# MotorController.net
KiCad netlist of a schematic drawn in EAGLE
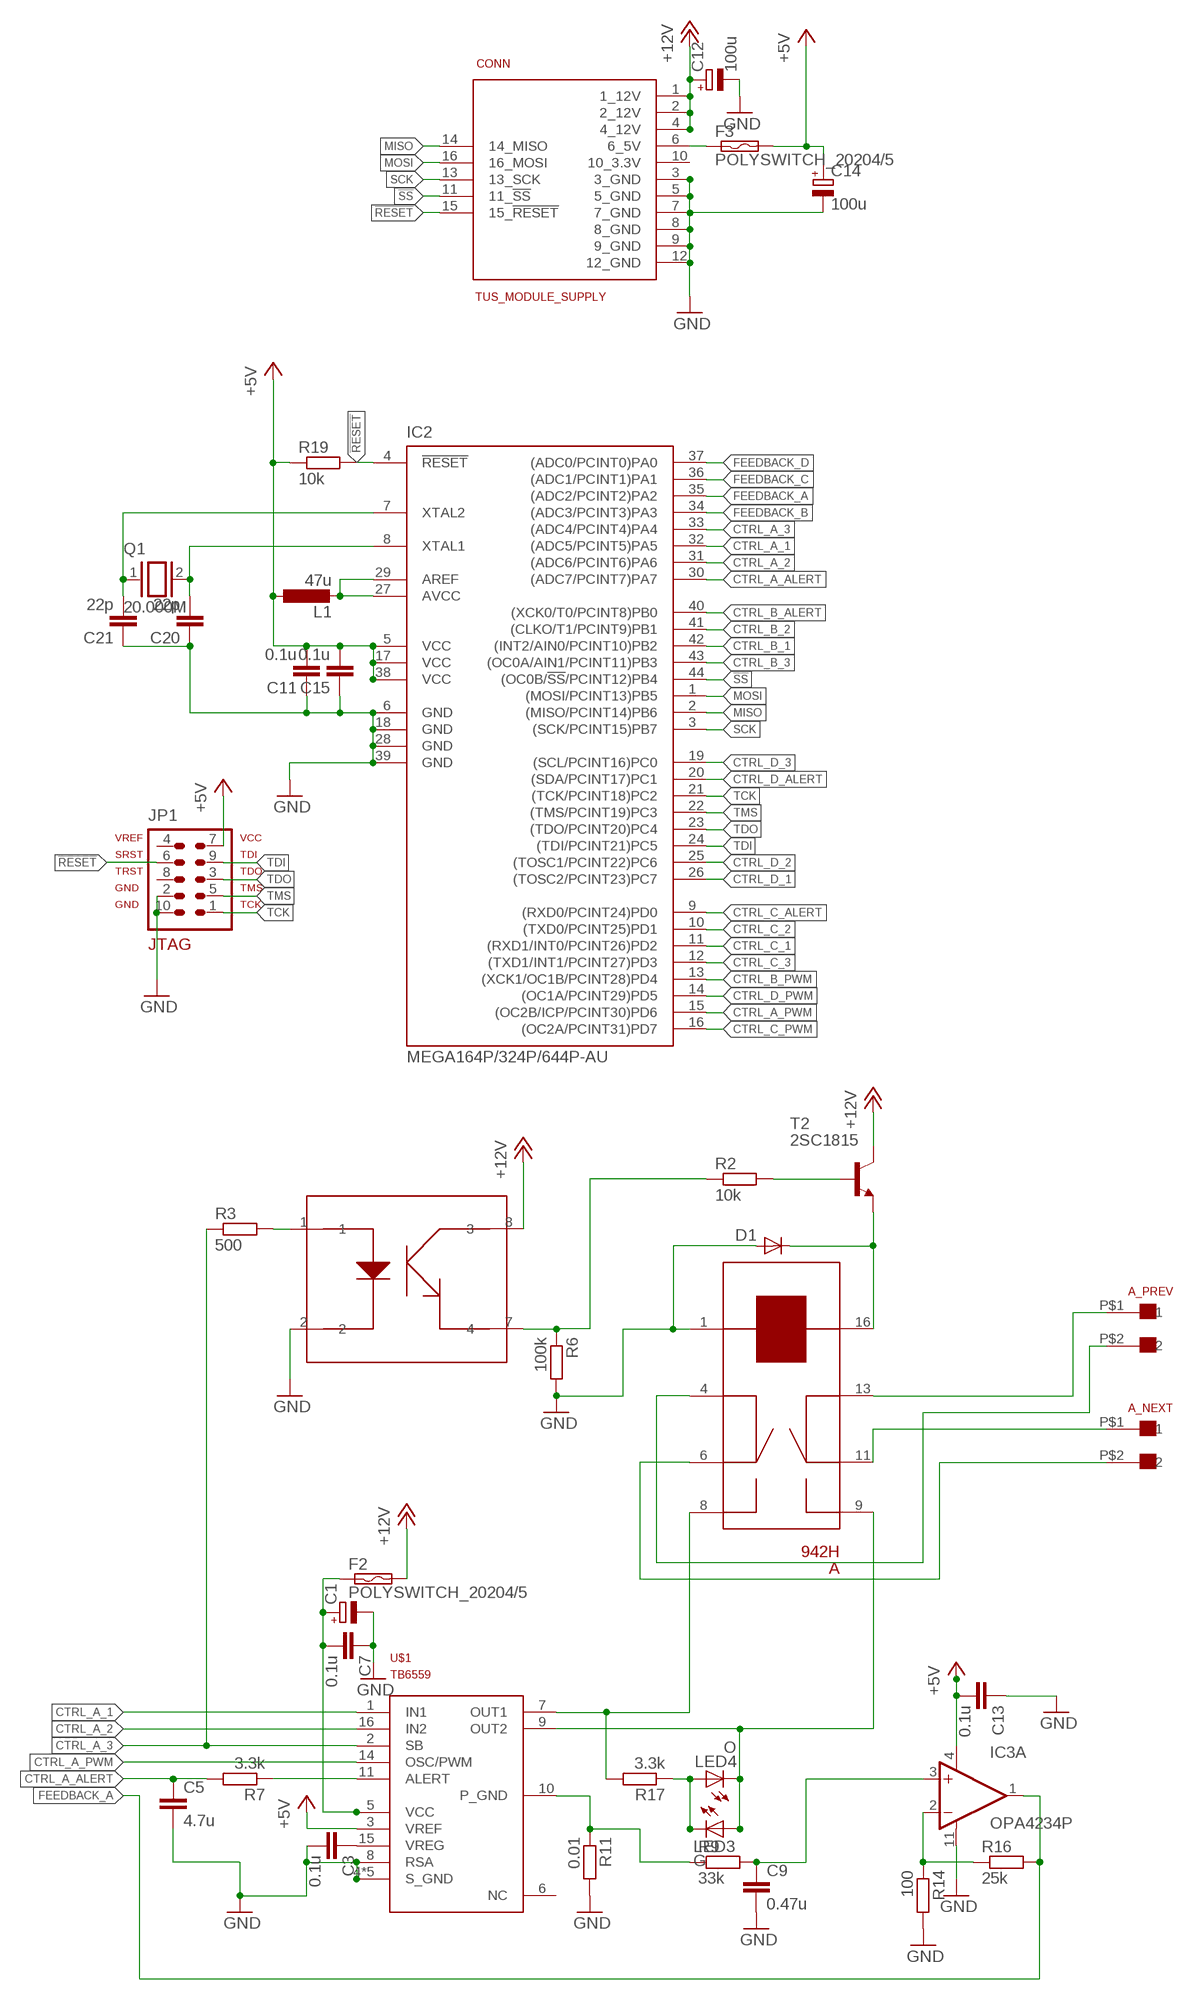
[diagram p0: schematic, sheet 1, part 1 of 2]
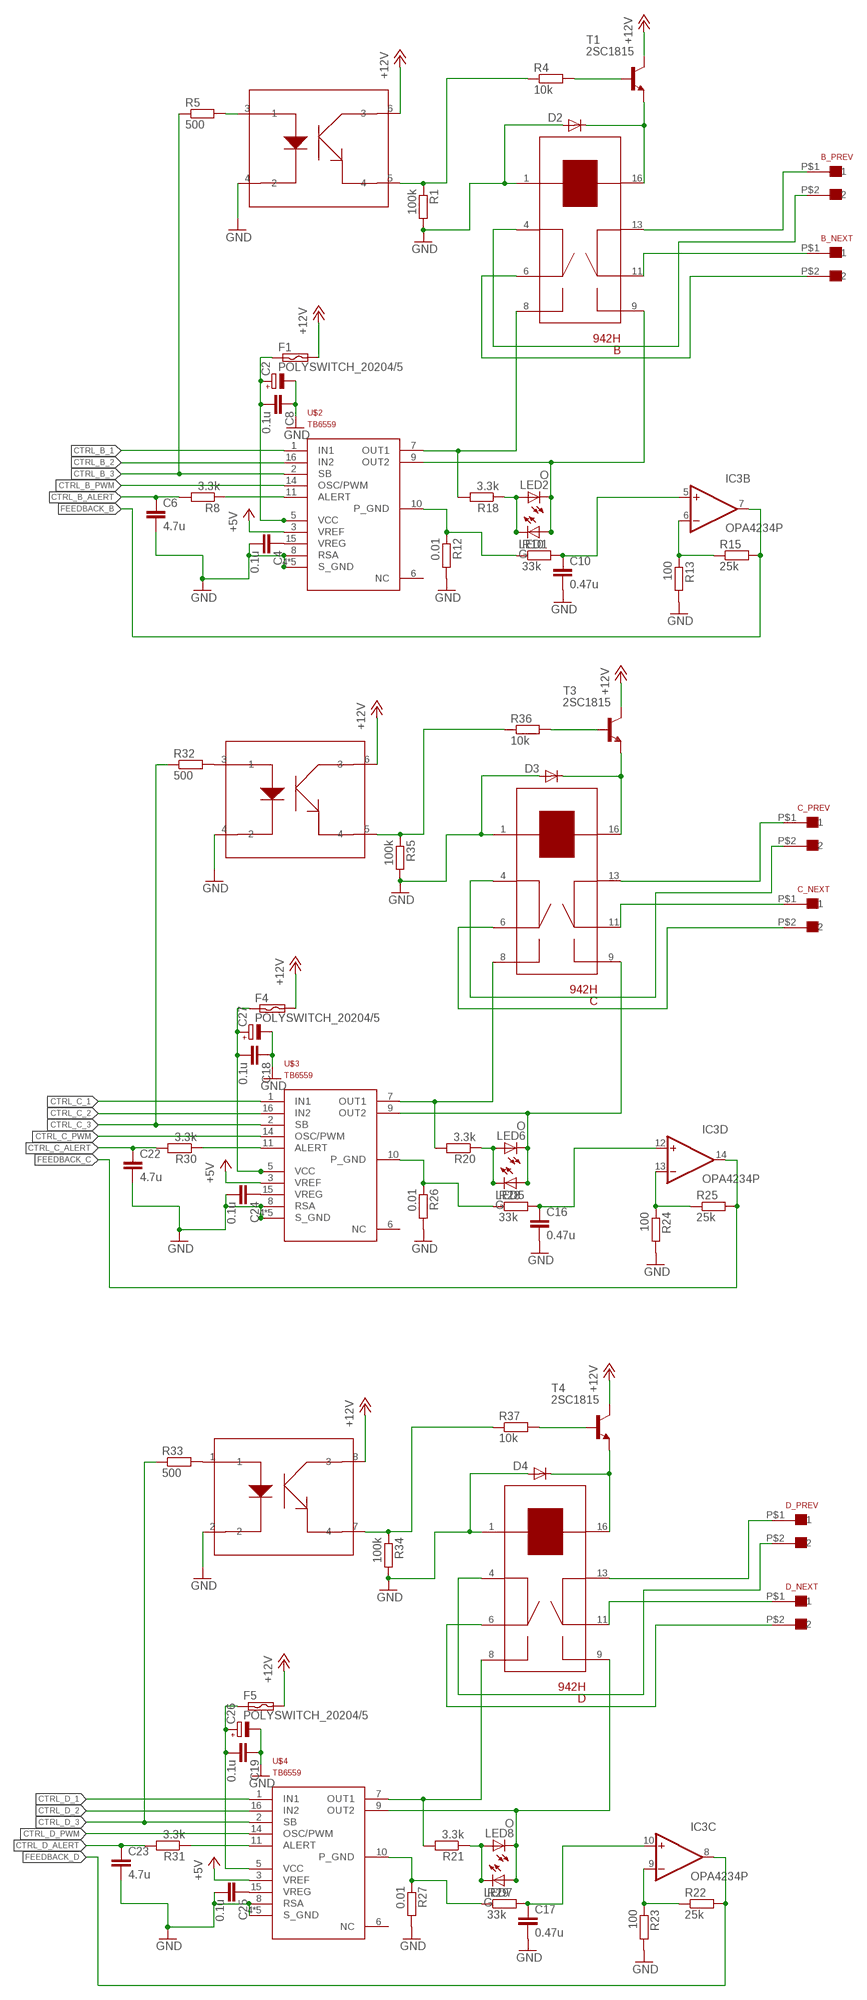
[diagram p1: schematic, sheet 1, part 2 of 2]

(export (version "E")
  (design (tool "Eeschema 10.0.6"))
  (components
    (comp (ref "A")
      (value "942H")
      (footprint "eagle-import:941H-2C-12D")
      (libsource (lib "eagle-import") (part "942H"))
    )
    (comp (ref "A_NEXT")
      (value "XH-2")
      (footprint "eagle-import:XH-2")
      (libsource (lib "eagle-import") (part "XH-2"))
    )
    (comp (ref "A_PREV")
      (value "XH-2")
      (footprint "eagle-import:XH-2")
      (libsource (lib "eagle-import") (part "XH-2"))
    )
    (comp (ref "B")
      (value "942H")
      (footprint "eagle-import:941H-2C-12D")
      (libsource (lib "eagle-import") (part "942H"))
    )
    (comp (ref "B_NEXT")
      (value "XH-2")
      (footprint "eagle-import:XH-2")
      (libsource (lib "eagle-import") (part "XH-2"))
    )
    (comp (ref "B_PREV")
      (value "XH-2")
      (footprint "eagle-import:XH-2")
      (libsource (lib "eagle-import") (part "XH-2"))
    )
    (comp (ref "C")
      (value "942H")
      (footprint "eagle-import:941H-2C-12D")
      (libsource (lib "eagle-import") (part "942H"))
    )
    (comp (ref "C1")
      (value "CPOL-EUE2,5-6E")
      (footprint "eagle-import:E2,5-6E")
      (libsource (lib "eagle-import") (part "CPOL-EUE2,5-6E"))
    )
    (comp (ref "C2")
      (value "CPOL-EUE2,5-6E")
      (footprint "eagle-import:E2,5-6E")
      (libsource (lib "eagle-import") (part "CPOL-EUE2,5-6E"))
    )
    (comp (ref "C3")
      (value "0.1u")
      (footprint "eagle-import:C0603")
      (libsource (lib "eagle-import") (part "C-EUC0603"))
    )
    (comp (ref "C4")
      (value "0.1u")
      (footprint "eagle-import:C0603")
      (libsource (lib "eagle-import") (part "C-EUC0603"))
    )
    (comp (ref "C5")
      (value "4.7u")
      (footprint "eagle-import:C0603")
      (libsource (lib "eagle-import") (part "C-EUC0603"))
    )
    (comp (ref "C6")
      (value "4.7u")
      (footprint "eagle-import:C0603")
      (libsource (lib "eagle-import") (part "C-EUC0603"))
    )
    (comp (ref "C7")
      (value "0.1u")
      (footprint "eagle-import:C0603")
      (libsource (lib "eagle-import") (part "C-EUC0603"))
    )
    (comp (ref "C8")
      (value "0.1u")
      (footprint "eagle-import:C0603")
      (libsource (lib "eagle-import") (part "C-EUC0603"))
    )
    (comp (ref "C9")
      (value "0.47u")
      (footprint "eagle-import:C0603")
      (libsource (lib "eagle-import") (part "C-EUC0603"))
    )
    (comp (ref "C10")
      (value "0.47u")
      (footprint "eagle-import:C0603")
      (libsource (lib "eagle-import") (part "C-EUC0603"))
    )
    (comp (ref "C11")
      (value "0.1u")
      (footprint "eagle-import:C0603")
      (libsource (lib "eagle-import") (part "C-EUC0603"))
    )
    (comp (ref "C12")
      (value "100u")
      (footprint "eagle-import:E2,5-6")
      (libsource (lib "eagle-import") (part "CPOL-EUE2.5-6"))
    )
    (comp (ref "C13")
      (value "0.1u")
      (footprint "eagle-import:C0603")
      (libsource (lib "eagle-import") (part "C-EUC0603"))
    )
    (comp (ref "C14")
      (value "100u")
      (footprint "eagle-import:E2-5")
      (libsource (lib "eagle-import") (part "CPOL-EUE2-5"))
    )
    (comp (ref "C15")
      (value "0.1u")
      (footprint "eagle-import:C0603")
      (libsource (lib "eagle-import") (part "C-EUC0603"))
    )
    (comp (ref "C16")
      (value "0.47u")
      (footprint "eagle-import:C0603")
      (libsource (lib "eagle-import") (part "C-EUC0603"))
    )
    (comp (ref "C17")
      (value "0.47u")
      (footprint "eagle-import:C0603")
      (libsource (lib "eagle-import") (part "C-EUC0603"))
    )
    (comp (ref "C18")
      (value "0.1u")
      (footprint "eagle-import:C0603")
      (libsource (lib "eagle-import") (part "C-EUC0603"))
    )
    (comp (ref "C19")
      (value "0.1u")
      (footprint "eagle-import:C0603")
      (libsource (lib "eagle-import") (part "C-EUC0603"))
    )
    (comp (ref "C20")
      (value "22p")
      (footprint "eagle-import:C0603")
      (libsource (lib "eagle-import") (part "C-EUC0603"))
    )
    (comp (ref "C21")
      (value "22p")
      (footprint "eagle-import:C0603")
      (libsource (lib "eagle-import") (part "C-EUC0603"))
    )
    (comp (ref "C22")
      (value "4.7u")
      (footprint "eagle-import:C0603")
      (libsource (lib "eagle-import") (part "C-EUC0603"))
    )
    (comp (ref "C23")
      (value "4.7u")
      (footprint "eagle-import:C0603")
      (libsource (lib "eagle-import") (part "C-EUC0603"))
    )
    (comp (ref "C24")
      (value "0.1u")
      (footprint "eagle-import:C0603")
      (libsource (lib "eagle-import") (part "C-EUC0603"))
    )
    (comp (ref "C25")
      (value "0.1u")
      (footprint "eagle-import:C0603")
      (libsource (lib "eagle-import") (part "C-EUC0603"))
    )
    (comp (ref "C26")
      (value "CPOL-EUE2,5-6E")
      (footprint "eagle-import:E2,5-6E")
      (libsource (lib "eagle-import") (part "CPOL-EUE2,5-6E"))
    )
    (comp (ref "C27")
      (value "CPOL-EUE2,5-6E")
      (footprint "eagle-import:E2,5-6E")
      (libsource (lib "eagle-import") (part "CPOL-EUE2,5-6E"))
    )
    (comp (ref "CONN")
      (value "TUS_MODULE_SUPPLY")
      (footprint "eagle-import:2X08")
      (libsource (lib "eagle-import") (part "TUS_MODULE_SUPPLY"))
    )
    (comp (ref "C_NEXT")
      (value "XH-2")
      (footprint "eagle-import:XH-2")
      (libsource (lib "eagle-import") (part "XH-2"))
    )
    (comp (ref "C_PREV")
      (value "XH-2")
      (footprint "eagle-import:XH-2")
      (libsource (lib "eagle-import") (part "XH-2"))
    )
    (comp (ref "D")
      (value "942H")
      (footprint "eagle-import:941H-2C-12D")
      (libsource (lib "eagle-import") (part "942H"))
    )
    (comp (ref "D1")
      (value "1N4148DO35-7")
      (footprint "eagle-import:DO35-7")
      (libsource (lib "eagle-import") (part "1N4148DO35-7"))
    )
    (comp (ref "D2")
      (value "1N4148DO35-7")
      (footprint "eagle-import:DO35-7")
      (libsource (lib "eagle-import") (part "1N4148DO35-7"))
    )
    (comp (ref "D3")
      (value "1N4148DO35-7")
      (footprint "eagle-import:DO35-7")
      (libsource (lib "eagle-import") (part "1N4148DO35-7"))
    )
    (comp (ref "D4")
      (value "1N4148DO35-7")
      (footprint "eagle-import:DO35-7")
      (libsource (lib "eagle-import") (part "1N4148DO35-7"))
    )
    (comp (ref "D_NEXT")
      (value "XH-2")
      (footprint "eagle-import:XH-2")
      (libsource (lib "eagle-import") (part "XH-2"))
    )
    (comp (ref "D_PREV")
      (value "XH-2")
      (footprint "eagle-import:XH-2")
      (libsource (lib "eagle-import") (part "XH-2"))
    )
    (comp (ref "F1")
      (value "POLYSWITCH_20204/5")
      (footprint "eagle-import:0204_5")
      (libsource (lib "eagle-import") (part "POLYSWITCH_20204/5"))
    )
    (comp (ref "F2")
      (value "POLYSWITCH_20204/5")
      (footprint "eagle-import:0204_5")
      (libsource (lib "eagle-import") (part "POLYSWITCH_20204/5"))
    )
    (comp (ref "F3")
      (value "POLYSWITCH_20204/5")
      (footprint "eagle-import:0204_5")
      (libsource (lib "eagle-import") (part "POLYSWITCH_20204/5"))
    )
    (comp (ref "F4")
      (value "POLYSWITCH_20204/5")
      (footprint "eagle-import:0204_5")
      (libsource (lib "eagle-import") (part "POLYSWITCH_20204/5"))
    )
    (comp (ref "F5")
      (value "POLYSWITCH_20204/5")
      (footprint "eagle-import:0204_5")
      (libsource (lib "eagle-import") (part "POLYSWITCH_20204/5"))
    )
    (comp (ref "IC1")
      (value "TLP621-2")
      (footprint "eagle-import:SOCKET-08")
      (libsource (lib "eagle-import") (part "TLP621-2"))
    )
    (comp (ref "IC2")
      (value "MEGA164P/324P/644P-AU")
      (footprint "eagle-import:TQFP44")
      (libsource (lib "eagle-import") (part "MEGA164P/324P/644P-AU"))
    )
    (comp (ref "IC3")
      (value "OPA4234P")
      (footprint "eagle-import:DIL14")
      (libsource (lib "eagle-import") (part "OPA4234P"))
    )
    (comp (ref "IC4")
      (value "TLP621-2")
      (footprint "eagle-import:SOCKET-08")
      (libsource (lib "eagle-import") (part "TLP621-2"))
    )
    (comp (ref "JP1")
      (value "AVR-JTAG-10")
      (footprint "eagle-import:AVR-JTAG-10")
      (libsource (lib "eagle-import") (part "AVR-JTAG-10"))
    )
    (comp (ref "L1")
      (value "47u")
      (footprint "eagle-import:L3216C")
      (libsource (lib "eagle-import") (part "L-EUL3216C"))
    )
    (comp (ref "LED1")
      (value "G")
      (footprint "eagle-import:LED3MM")
      (libsource (lib "eagle-import") (part "LED3MM"))
    )
    (comp (ref "LED2")
      (value "O")
      (footprint "eagle-import:LED3MM")
      (libsource (lib "eagle-import") (part "LED3MM"))
    )
    (comp (ref "LED3")
      (value "G")
      (footprint "eagle-import:LED3MM")
      (libsource (lib "eagle-import") (part "LED3MM"))
    )
    (comp (ref "LED4")
      (value "O")
      (footprint "eagle-import:LED3MM")
      (libsource (lib "eagle-import") (part "LED3MM"))
    )
    (comp (ref "LED5")
      (value "G")
      (footprint "eagle-import:LED3MM")
      (libsource (lib "eagle-import") (part "LED3MM"))
    )
    (comp (ref "LED6")
      (value "O")
      (footprint "eagle-import:LED3MM")
      (libsource (lib "eagle-import") (part "LED3MM"))
    )
    (comp (ref "LED7")
      (value "G")
      (footprint "eagle-import:LED3MM")
      (libsource (lib "eagle-import") (part "LED3MM"))
    )
    (comp (ref "LED8")
      (value "O")
      (footprint "eagle-import:LED3MM")
      (libsource (lib "eagle-import") (part "LED3MM"))
    )
    (comp (ref "Q1")
      (value "20.000M")
      (footprint "eagle-import:QS")
      (libsource (lib "eagle-import") (part "XTAL/S"))
    )
    (comp (ref "R1")
      (value "100k")
      (footprint "eagle-import:R0603")
      (libsource (lib "eagle-import") (part "R-EU_R0603"))
    )
    (comp (ref "R2")
      (value "10k")
      (footprint "eagle-import:R0603")
      (libsource (lib "eagle-import") (part "R-EU_R0603"))
    )
    (comp (ref "R3")
      (value "500")
      (footprint "eagle-import:R0603")
      (libsource (lib "eagle-import") (part "R-EU_R0603"))
    )
    (comp (ref "R4")
      (value "10k")
      (footprint "eagle-import:R0603")
      (libsource (lib "eagle-import") (part "R-EU_R0603"))
    )
    (comp (ref "R5")
      (value "500")
      (footprint "eagle-import:R0603")
      (libsource (lib "eagle-import") (part "R-EU_R0603"))
    )
    (comp (ref "R6")
      (value "100k")
      (footprint "eagle-import:R0603")
      (libsource (lib "eagle-import") (part "R-EU_R0603"))
    )
    (comp (ref "R7")
      (value "3.3k")
      (footprint "eagle-import:R0603")
      (libsource (lib "eagle-import") (part "R-EU_R0603"))
    )
    (comp (ref "R8")
      (value "3.3k")
      (footprint "eagle-import:R0603")
      (libsource (lib "eagle-import") (part "R-EU_R0603"))
    )
    (comp (ref "R9")
      (value "33k")
      (footprint "eagle-import:R0603")
      (libsource (lib "eagle-import") (part "R-EU_R0603"))
    )
    (comp (ref "R10")
      (value "33k")
      (footprint "eagle-import:R0603")
      (libsource (lib "eagle-import") (part "R-EU_R0603"))
    )
    (comp (ref "R11")
      (value "0.01")
      (footprint "eagle-import:R1206")
      (libsource (lib "eagle-import") (part "R-EU_R1206"))
    )
    (comp (ref "R12")
      (value "0.01")
      (footprint "eagle-import:R1206")
      (libsource (lib "eagle-import") (part "R-EU_R1206"))
    )
    (comp (ref "R13")
      (value "100")
      (footprint "eagle-import:R0603")
      (libsource (lib "eagle-import") (part "R-EU_R0603"))
    )
    (comp (ref "R14")
      (value "100")
      (footprint "eagle-import:R0603")
      (libsource (lib "eagle-import") (part "R-EU_R0603"))
    )
    (comp (ref "R15")
      (value "25k")
      (footprint "eagle-import:R0603")
      (libsource (lib "eagle-import") (part "R-EU_R0603"))
    )
    (comp (ref "R16")
      (value "25k")
      (footprint "eagle-import:R0603")
      (libsource (lib "eagle-import") (part "R-EU_R0603"))
    )
    (comp (ref "R17")
      (value "3.3k")
      (footprint "eagle-import:R0603")
      (libsource (lib "eagle-import") (part "R-EU_R0603"))
    )
    (comp (ref "R18")
      (value "3.3k")
      (footprint "eagle-import:R0603")
      (libsource (lib "eagle-import") (part "R-EU_R0603"))
    )
    (comp (ref "R19")
      (value "10k")
      (footprint "eagle-import:R0603")
      (libsource (lib "eagle-import") (part "R-EU_R0603"))
    )
    (comp (ref "R20")
      (value "3.3k")
      (footprint "eagle-import:R0603")
      (libsource (lib "eagle-import") (part "R-EU_R0603"))
    )
    (comp (ref "R21")
      (value "3.3k")
      (footprint "eagle-import:R0603")
      (libsource (lib "eagle-import") (part "R-EU_R0603"))
    )
    (comp (ref "R22")
      (value "25k")
      (footprint "eagle-import:R0603")
      (libsource (lib "eagle-import") (part "R-EU_R0603"))
    )
    (comp (ref "R23")
      (value "100")
      (footprint "eagle-import:R0603")
      (libsource (lib "eagle-import") (part "R-EU_R0603"))
    )
    (comp (ref "R24")
      (value "100")
      (footprint "eagle-import:R0603")
      (libsource (lib "eagle-import") (part "R-EU_R0603"))
    )
    (comp (ref "R25")
      (value "25k")
      (footprint "eagle-import:R0603")
      (libsource (lib "eagle-import") (part "R-EU_R0603"))
    )
    (comp (ref "R26")
      (value "0.01")
      (footprint "eagle-import:R1206")
      (libsource (lib "eagle-import") (part "R-EU_R1206"))
    )
    (comp (ref "R27")
      (value "0.01")
      (footprint "eagle-import:R1206")
      (libsource (lib "eagle-import") (part "R-EU_R1206"))
    )
    (comp (ref "R28")
      (value "33k")
      (footprint "eagle-import:R0603")
      (libsource (lib "eagle-import") (part "R-EU_R0603"))
    )
    (comp (ref "R29")
      (value "33k")
      (footprint "eagle-import:R0603")
      (libsource (lib "eagle-import") (part "R-EU_R0603"))
    )
    (comp (ref "R30")
      (value "3.3k")
      (footprint "eagle-import:R0603")
      (libsource (lib "eagle-import") (part "R-EU_R0603"))
    )
    (comp (ref "R31")
      (value "3.3k")
      (footprint "eagle-import:R0603")
      (libsource (lib "eagle-import") (part "R-EU_R0603"))
    )
    (comp (ref "R32")
      (value "500")
      (footprint "eagle-import:R0603")
      (libsource (lib "eagle-import") (part "R-EU_R0603"))
    )
    (comp (ref "R33")
      (value "500")
      (footprint "eagle-import:R0603")
      (libsource (lib "eagle-import") (part "R-EU_R0603"))
    )
    (comp (ref "R34")
      (value "100k")
      (footprint "eagle-import:R0603")
      (libsource (lib "eagle-import") (part "R-EU_R0603"))
    )
    (comp (ref "R35")
      (value "100k")
      (footprint "eagle-import:R0603")
      (libsource (lib "eagle-import") (part "R-EU_R0603"))
    )
    (comp (ref "R36")
      (value "10k")
      (footprint "eagle-import:R0603")
      (libsource (lib "eagle-import") (part "R-EU_R0603"))
    )
    (comp (ref "R37")
      (value "10k")
      (footprint "eagle-import:R0603")
      (libsource (lib "eagle-import") (part "R-EU_R0603"))
    )
    (comp (ref "T1")
      (value "2SC1815")
      (footprint "eagle-import:TO92-ECB")
      (libsource (lib "eagle-import") (part "2SC1815"))
    )
    (comp (ref "T2")
      (value "2SC1815")
      (footprint "eagle-import:TO92-ECB")
      (libsource (lib "eagle-import") (part "2SC1815"))
    )
    (comp (ref "T3")
      (value "2SC1815")
      (footprint "eagle-import:TO92-ECB")
      (libsource (lib "eagle-import") (part "2SC1815"))
    )
    (comp (ref "T4")
      (value "2SC1815")
      (footprint "eagle-import:TO92-ECB")
      (libsource (lib "eagle-import") (part "2SC1815"))
    )
    (comp (ref "U$1")
      (value "TB6559")
      (footprint "eagle-import:HSOP-16")
      (libsource (lib "eagle-import") (part "TB6559"))
    )
    (comp (ref "U$2")
      (value "TB6559")
      (footprint "eagle-import:HSOP-16")
      (libsource (lib "eagle-import") (part "TB6559"))
    )
    (comp (ref "U$3")
      (value "TB6559")
      (footprint "eagle-import:HSOP-16")
      (libsource (lib "eagle-import") (part "TB6559"))
    )
    (comp (ref "U$4")
      (value "TB6559")
      (footprint "eagle-import:HSOP-16")
      (libsource (lib "eagle-import") (part "TB6559"))
    )
  )
  (nets
    (net (code "1") (name "+5V") (class "Default")
      (node (ref "C11") (pin "2") (pinfunction "2_2") (pintype "passive"))
      (node (ref "C13") (pin "2") (pinfunction "2_2") (pintype "passive"))
      (node (ref "C14") (pin "+") (pinfunction "+_+") (pintype "passive"))
      (node (ref "C15") (pin "2") (pinfunction "2_2") (pintype "passive"))
      (node (ref "F3") (pin "2") (pinfunction "2_2") (pintype "passive"))
      (node (ref "IC2") (pin "17") (pinfunction "VCC_17") (pintype "power_in"))
      (node (ref "IC2") (pin "38") (pinfunction "VCC_38") (pintype "power_in"))
      (node (ref "IC2") (pin "5") (pinfunction "VCC_5") (pintype "power_in"))
      (node (ref "IC3") (pin "4") (pinfunction "V+_4") (pintype "power_in"))
      (node (ref "JP1") (pin "7") (pinfunction "7_7") (pintype "passive"))
      (node (ref "L1") (pin "1") (pinfunction "1_1") (pintype "passive"))
      (node (ref "R19") (pin "1") (pinfunction "1_1") (pintype "passive"))
      (node (ref "U$1") (pin "3") (pinfunction "VREF_3") (pintype "bidirectional"))
      (node (ref "U$2") (pin "3") (pinfunction "VREF_3") (pintype "bidirectional"))
      (node (ref "U$3") (pin "3") (pinfunction "VREF_3") (pintype "bidirectional"))
      (node (ref "U$4") (pin "3") (pinfunction "VREF_3") (pintype "bidirectional"))
    )
    (net (code "2") (name "+12V") (class "Default")
      (node (ref "C12") (pin "+") (pinfunction "+_+") (pintype "passive"))
      (node (ref "CONN") (pin "1") (pinfunction "1_12V_1") (pintype "bidirectional"))
      (node (ref "CONN") (pin "2") (pinfunction "2_12V_2") (pintype "bidirectional"))
      (node (ref "CONN") (pin "4") (pinfunction "4_12V_4") (pintype "bidirectional"))
      (node (ref "F1") (pin "2") (pinfunction "2_2") (pintype "passive"))
      (node (ref "F2") (pin "2") (pinfunction "2_2") (pintype "passive"))
      (node (ref "F4") (pin "2") (pinfunction "2_2") (pintype "passive"))
      (node (ref "F5") (pin "2") (pinfunction "2_2") (pintype "passive"))
      (node (ref "IC1") (pin "6") (pinfunction "3_6") (pintype "bidirectional"))
      (node (ref "IC1") (pin "8") (pinfunction "3_8") (pintype "bidirectional"))
      (node (ref "IC4") (pin "6") (pinfunction "3_6") (pintype "bidirectional"))
      (node (ref "IC4") (pin "8") (pinfunction "3_8") (pintype "bidirectional"))
      (node (ref "T1") (pin "C") (pinfunction "C_C") (pintype "passive"))
      (node (ref "T2") (pin "C") (pinfunction "C_C") (pintype "passive"))
      (node (ref "T3") (pin "C") (pinfunction "C_C") (pintype "passive"))
      (node (ref "T4") (pin "C") (pinfunction "C_C") (pintype "passive"))
    )
    (net (code "3") (name "/~{RESET}") (class "Default")
      (node (ref "CONN") (pin "15") (pinfunction "15_~{RESET}_15") (pintype "bidirectional"))
      (node (ref "IC2") (pin "4") (pinfunction "~{RESET}_4") (pintype "input"))
      (node (ref "JP1") (pin "6") (pinfunction "6_6") (pintype "passive"))
      (node (ref "R19") (pin "2") (pinfunction "2_2") (pintype "passive"))
    )
    (net (code "4") (name "/~{SS}") (class "Default")
      (node (ref "CONN") (pin "11") (pinfunction "11_~{SS}_11") (pintype "bidirectional"))
      (node (ref "IC2") (pin "44") (pinfunction "(OC0B/~{SS}/PCINT12)PB4_44") (pintype "bidirectional"))
    )
    (net (code "5") (name "CTRL_A_1") (class "Default")
      (node (ref "IC2") (pin "32") (pinfunction "(ADC5/PCINT5)PA5_32") (pintype "bidirectional"))
      (node (ref "U$1") (pin "1") (pinfunction "IN1_1") (pintype "bidirectional"))
    )
    (net (code "6") (name "CTRL_A_2") (class "Default")
      (node (ref "IC2") (pin "31") (pinfunction "(ADC6/PCINT6)PA6_31") (pintype "bidirectional"))
      (node (ref "U$1") (pin "16") (pinfunction "IN2_16") (pintype "bidirectional"))
    )
    (net (code "7") (name "CTRL_A_3") (class "Default")
      (node (ref "IC2") (pin "33") (pinfunction "(ADC4/PCINT4)PA4_33") (pintype "bidirectional"))
      (node (ref "R3") (pin "1") (pinfunction "1_1") (pintype "passive"))
      (node (ref "U$1") (pin "2") (pinfunction "SB_2") (pintype "bidirectional"))
    )
    (net (code "8") (name "CTRL_A_ALERT") (class "Default")
      (node (ref "C5") (pin "1") (pinfunction "1_1") (pintype "passive"))
      (node (ref "IC2") (pin "30") (pinfunction "(ADC7/PCINT7)PA7_30") (pintype "bidirectional"))
      (node (ref "R7") (pin "2") (pinfunction "2_2") (pintype "passive"))
    )
    (net (code "9") (name "CTRL_A_PWM") (class "Default")
      (node (ref "IC2") (pin "15") (pinfunction "(OC2B/ICP/PCINT30)PD6_15") (pintype "bidirectional"))
      (node (ref "U$1") (pin "14") (pinfunction "OSC/PWM_14") (pintype "bidirectional"))
    )
    (net (code "10") (name "CTRL_B_1") (class "Default")
      (node (ref "IC2") (pin "42") (pinfunction "(INT2/AIN0/PCINT10)PB2_42") (pintype "bidirectional"))
      (node (ref "U$2") (pin "1") (pinfunction "IN1_1") (pintype "bidirectional"))
    )
    (net (code "11") (name "CTRL_B_2") (class "Default")
      (node (ref "IC2") (pin "41") (pinfunction "(CLKO/T1/PCINT9)PB1_41") (pintype "bidirectional"))
      (node (ref "U$2") (pin "16") (pinfunction "IN2_16") (pintype "bidirectional"))
    )
    (net (code "12") (name "CTRL_B_3") (class "Default")
      (node (ref "IC2") (pin "43") (pinfunction "(OC0A/AIN1/PCINT11)PB3_43") (pintype "bidirectional"))
      (node (ref "R5") (pin "1") (pinfunction "1_1") (pintype "passive"))
      (node (ref "U$2") (pin "2") (pinfunction "SB_2") (pintype "bidirectional"))
    )
    (net (code "13") (name "CTRL_B_ALERT") (class "Default")
      (node (ref "C6") (pin "1") (pinfunction "1_1") (pintype "passive"))
      (node (ref "IC2") (pin "40") (pinfunction "(XCK0/T0/PCINT8)PB0_40") (pintype "bidirectional"))
      (node (ref "R8") (pin "2") (pinfunction "2_2") (pintype "passive"))
    )
    (net (code "14") (name "CTRL_B_PWM") (class "Default")
      (node (ref "IC2") (pin "13") (pinfunction "(XCK1/OC1B/PCINT28)PD4_13") (pintype "bidirectional"))
      (node (ref "U$2") (pin "14") (pinfunction "OSC/PWM_14") (pintype "bidirectional"))
    )
    (net (code "15") (name "CTRL_C_1") (class "Default")
      (node (ref "IC2") (pin "11") (pinfunction "(RXD1/INT0/PCINT26)PD2_11") (pintype "bidirectional"))
      (node (ref "U$3") (pin "1") (pinfunction "IN1_1") (pintype "bidirectional"))
    )
    (net (code "16") (name "CTRL_C_2") (class "Default")
      (node (ref "IC2") (pin "10") (pinfunction "(TXD0/PCINT25)PD1_10") (pintype "bidirectional"))
      (node (ref "U$3") (pin "16") (pinfunction "IN2_16") (pintype "bidirectional"))
    )
    (net (code "17") (name "CTRL_C_3") (class "Default")
      (node (ref "IC2") (pin "12") (pinfunction "(TXD1/INT1/PCINT27)PD3_12") (pintype "bidirectional"))
      (node (ref "R32") (pin "1") (pinfunction "1_1") (pintype "passive"))
      (node (ref "U$3") (pin "2") (pinfunction "SB_2") (pintype "bidirectional"))
    )
    (net (code "18") (name "CTRL_C_ALERT") (class "Default")
      (node (ref "C22") (pin "1") (pinfunction "1_1") (pintype "passive"))
      (node (ref "IC2") (pin "9") (pinfunction "(RXD0/PCINT24)PD0_9") (pintype "bidirectional"))
      (node (ref "R30") (pin "2") (pinfunction "2_2") (pintype "passive"))
    )
    (net (code "19") (name "CTRL_C_PWM") (class "Default")
      (node (ref "IC2") (pin "16") (pinfunction "(OC2A/PCINT31)PD7_16") (pintype "bidirectional"))
      (node (ref "U$3") (pin "14") (pinfunction "OSC/PWM_14") (pintype "bidirectional"))
    )
    (net (code "20") (name "CTRL_D_1") (class "Default")
      (node (ref "IC2") (pin "26") (pinfunction "(TOSC2/PCINT23)PC7_26") (pintype "bidirectional"))
      (node (ref "U$4") (pin "1") (pinfunction "IN1_1") (pintype "bidirectional"))
    )
    (net (code "21") (name "CTRL_D_2") (class "Default")
      (node (ref "IC2") (pin "25") (pinfunction "(TOSC1/PCINT22)PC6_25") (pintype "bidirectional"))
      (node (ref "U$4") (pin "16") (pinfunction "IN2_16") (pintype "bidirectional"))
    )
    (net (code "22") (name "CTRL_D_3") (class "Default")
      (node (ref "IC2") (pin "19") (pinfunction "(SCL/PCINT16)PC0_19") (pintype "bidirectional"))
      (node (ref "R33") (pin "1") (pinfunction "1_1") (pintype "passive"))
      (node (ref "U$4") (pin "2") (pinfunction "SB_2") (pintype "bidirectional"))
    )
    (net (code "23") (name "CTRL_D_ALERT") (class "Default")
      (node (ref "C23") (pin "1") (pinfunction "1_1") (pintype "passive"))
      (node (ref "IC2") (pin "20") (pinfunction "(SDA/PCINT17)PC1_20") (pintype "bidirectional"))
      (node (ref "R31") (pin "2") (pinfunction "2_2") (pintype "passive"))
    )
    (net (code "24") (name "CTRL_D_PWM") (class "Default")
      (node (ref "IC2") (pin "14") (pinfunction "(OC1A/PCINT29)PD5_14") (pintype "bidirectional"))
      (node (ref "U$4") (pin "14") (pinfunction "OSC/PWM_14") (pintype "bidirectional"))
    )
    (net (code "25") (name "FEEDBACK_A") (class "Default")
      (node (ref "IC2") (pin "35") (pinfunction "(ADC2/PCINT2)PA2_35") (pintype "bidirectional"))
      (node (ref "IC3") (pin "1") (pinfunction "OUT_1") (pintype "output"))
      (node (ref "R16") (pin "2") (pinfunction "2_2") (pintype "passive"))
    )
    (net (code "26") (name "FEEDBACK_B") (class "Default")
      (node (ref "IC2") (pin "34") (pinfunction "(ADC3/PCINT3)PA3_34") (pintype "bidirectional"))
      (node (ref "IC3") (pin "7") (pinfunction "OUT_7") (pintype "output"))
      (node (ref "R15") (pin "2") (pinfunction "2_2") (pintype "passive"))
    )
    (net (code "27") (name "FEEDBACK_C") (class "Default")
      (node (ref "IC2") (pin "36") (pinfunction "(ADC1/PCINT1)PA1_36") (pintype "bidirectional"))
      (node (ref "IC3") (pin "14") (pinfunction "OUT_14") (pintype "output"))
      (node (ref "R25") (pin "2") (pinfunction "2_2") (pintype "passive"))
    )
    (net (code "28") (name "FEEDBACK_D") (class "Default")
      (node (ref "IC2") (pin "37") (pinfunction "(ADC0/PCINT0)PA0_37") (pintype "bidirectional"))
      (node (ref "IC3") (pin "8") (pinfunction "OUT_8") (pintype "output"))
      (node (ref "R22") (pin "2") (pinfunction "2_2") (pintype "passive"))
    )
    (net (code "29") (name "GND") (class "Default")
      (node (ref "A") (pin "1") (pinfunction "4_1") (pintype "bidirectional"))
      (node (ref "B") (pin "1") (pinfunction "4_1") (pintype "bidirectional"))
      (node (ref "C") (pin "1") (pinfunction "4_1") (pintype "bidirectional"))
      (node (ref "C1") (pin "-") (pinfunction "-_-") (pintype "passive"))
      (node (ref "C10") (pin "2") (pinfunction "2_2") (pintype "passive"))
      (node (ref "C11") (pin "1") (pinfunction "1_1") (pintype "passive"))
      (node (ref "C12") (pin "-") (pinfunction "-_-") (pintype "passive"))
      (node (ref "C13") (pin "1") (pinfunction "1_1") (pintype "passive"))
      (node (ref "C14") (pin "-") (pinfunction "-_-") (pintype "passive"))
      (node (ref "C15") (pin "1") (pinfunction "1_1") (pintype "passive"))
      (node (ref "C16") (pin "2") (pinfunction "2_2") (pintype "passive"))
      (node (ref "C17") (pin "2") (pinfunction "2_2") (pintype "passive"))
      (node (ref "C18") (pin "1") (pinfunction "1_1") (pintype "passive"))
      (node (ref "C19") (pin "1") (pinfunction "1_1") (pintype "passive"))
      (node (ref "C2") (pin "-") (pinfunction "-_-") (pintype "passive"))
      (node (ref "C20") (pin "1") (pinfunction "1_1") (pintype "passive"))
      (node (ref "C21") (pin "1") (pinfunction "1_1") (pintype "passive"))
      (node (ref "C22") (pin "2") (pinfunction "2_2") (pintype "passive"))
      (node (ref "C23") (pin "2") (pinfunction "2_2") (pintype "passive"))
      (node (ref "C24") (pin "2") (pinfunction "2_2") (pintype "passive"))
      (node (ref "C25") (pin "2") (pinfunction "2_2") (pintype "passive"))
      (node (ref "C26") (pin "-") (pinfunction "-_-") (pintype "passive"))
      (node (ref "C27") (pin "-") (pinfunction "-_-") (pintype "passive"))
      (node (ref "C3") (pin "2") (pinfunction "2_2") (pintype "passive"))
      (node (ref "C4") (pin "2") (pinfunction "2_2") (pintype "passive"))
      (node (ref "C5") (pin "2") (pinfunction "2_2") (pintype "passive"))
      (node (ref "C6") (pin "2") (pinfunction "2_2") (pintype "passive"))
      (node (ref "C7") (pin "1") (pinfunction "1_1") (pintype "passive"))
      (node (ref "C8") (pin "1") (pinfunction "1_1") (pintype "passive"))
      (node (ref "C9") (pin "2") (pinfunction "2_2") (pintype "passive"))
      (node (ref "CONN") (pin "12") (pinfunction "12_GND_12") (pintype "bidirectional"))
      (node (ref "CONN") (pin "3") (pinfunction "3_GND_3") (pintype "bidirectional"))
      (node (ref "CONN") (pin "5") (pinfunction "5_GND_5") (pintype "bidirectional"))
      (node (ref "CONN") (pin "7") (pinfunction "7_GND_7") (pintype "bidirectional"))
      (node (ref "CONN") (pin "8") (pinfunction "8_GND_8") (pintype "bidirectional"))
      (node (ref "CONN") (pin "9") (pinfunction "9_GND_9") (pintype "bidirectional"))
      (node (ref "D") (pin "1") (pinfunction "4_1") (pintype "bidirectional"))
      (node (ref "D1") (pin "A") (pinfunction "A_A") (pintype "passive"))
      (node (ref "D2") (pin "A") (pinfunction "A_A") (pintype "passive"))
      (node (ref "D3") (pin "A") (pinfunction "A_A") (pintype "passive"))
      (node (ref "D4") (pin "A") (pinfunction "A_A") (pintype "passive"))
      (node (ref "IC1") (pin "2") (pinfunction "2_2") (pintype "bidirectional"))
      (node (ref "IC1") (pin "4") (pinfunction "2_4") (pintype "bidirectional"))
      (node (ref "IC2") (pin "18") (pinfunction "GND_18") (pintype "power_in"))
      (node (ref "IC2") (pin "28") (pinfunction "GND_28") (pintype "power_in"))
      (node (ref "IC2") (pin "39") (pinfunction "GND_39") (pintype "power_in"))
      (node (ref "IC2") (pin "6") (pinfunction "GND_6") (pintype "power_in"))
      (node (ref "IC3") (pin "11") (pinfunction "V-_11") (pintype "power_in"))
      (node (ref "IC4") (pin "2") (pinfunction "2_2") (pintype "bidirectional"))
      (node (ref "IC4") (pin "4") (pinfunction "2_4") (pintype "bidirectional"))
      (node (ref "JP1") (pin "10") (pinfunction "10_10") (pintype "passive"))
      (node (ref "JP1") (pin "2") (pinfunction "2_2") (pintype "passive"))
      (node (ref "R1") (pin "2") (pinfunction "2_2") (pintype "passive"))
      (node (ref "R11") (pin "2") (pinfunction "2_2") (pintype "passive"))
      (node (ref "R12") (pin "2") (pinfunction "2_2") (pintype "passive"))
      (node (ref "R13") (pin "2") (pinfunction "2_2") (pintype "passive"))
      (node (ref "R14") (pin "2") (pinfunction "2_2") (pintype "passive"))
      (node (ref "R23") (pin "2") (pinfunction "2_2") (pintype "passive"))
      (node (ref "R24") (pin "2") (pinfunction "2_2") (pintype "passive"))
      (node (ref "R26") (pin "2") (pinfunction "2_2") (pintype "passive"))
      (node (ref "R27") (pin "2") (pinfunction "2_2") (pintype "passive"))
      (node (ref "R34") (pin "2") (pinfunction "2_2") (pintype "passive"))
      (node (ref "R35") (pin "2") (pinfunction "2_2") (pintype "passive"))
      (node (ref "R6") (pin "2") (pinfunction "2_2") (pintype "passive"))
      (node (ref "U$1") (pin "12") (pinfunction "S_GND_12") (pintype "bidirectional"))
      (node (ref "U$1") (pin "13") (pinfunction "S_GND_13") (pintype "bidirectional"))
      (node (ref "U$1") (pin "4") (pinfunction "S_GND_4") (pintype "bidirectional"))
      (node (ref "U$1") (pin "8") (pinfunction "RSA_8") (pintype "bidirectional"))
      (node (ref "U$1") (pin "FIN_1") (pinfunction "S_GND_FIN_1") (pintype "bidirectional"))
      (node (ref "U$1") (pin "FIN_2") (pinfunction "S_GND_FIN_2") (pintype "bidirectional"))
      (node (ref "U$2") (pin "12") (pinfunction "S_GND_12") (pintype "bidirectional"))
      (node (ref "U$2") (pin "13") (pinfunction "S_GND_13") (pintype "bidirectional"))
      (node (ref "U$2") (pin "4") (pinfunction "S_GND_4") (pintype "bidirectional"))
      (node (ref "U$2") (pin "8") (pinfunction "RSA_8") (pintype "bidirectional"))
      (node (ref "U$2") (pin "FIN_1") (pinfunction "S_GND_FIN_1") (pintype "bidirectional"))
      (node (ref "U$2") (pin "FIN_2") (pinfunction "S_GND_FIN_2") (pintype "bidirectional"))
      (node (ref "U$3") (pin "12") (pinfunction "S_GND_12") (pintype "bidirectional"))
      (node (ref "U$3") (pin "13") (pinfunction "S_GND_13") (pintype "bidirectional"))
      (node (ref "U$3") (pin "4") (pinfunction "S_GND_4") (pintype "bidirectional"))
      (node (ref "U$3") (pin "8") (pinfunction "RSA_8") (pintype "bidirectional"))
      (node (ref "U$3") (pin "FIN_1") (pinfunction "S_GND_FIN_1") (pintype "bidirectional"))
      (node (ref "U$3") (pin "FIN_2") (pinfunction "S_GND_FIN_2") (pintype "bidirectional"))
      (node (ref "U$4") (pin "12") (pinfunction "S_GND_12") (pintype "bidirectional"))
      (node (ref "U$4") (pin "13") (pinfunction "S_GND_13") (pintype "bidirectional"))
      (node (ref "U$4") (pin "4") (pinfunction "S_GND_4") (pintype "bidirectional"))
      (node (ref "U$4") (pin "8") (pinfunction "RSA_8") (pintype "bidirectional"))
      (node (ref "U$4") (pin "FIN_1") (pinfunction "S_GND_FIN_1") (pintype "bidirectional"))
      (node (ref "U$4") (pin "FIN_2") (pinfunction "S_GND_FIN_2") (pintype "bidirectional"))
    )
    (net (code "30") (name "MISO") (class "Default")
      (node (ref "CONN") (pin "14") (pinfunction "14_MISO_14") (pintype "bidirectional"))
      (node (ref "IC2") (pin "2") (pinfunction "(MISO/PCINT14)PB6_2") (pintype "bidirectional"))
    )
    (net (code "31") (name "MOSI") (class "Default")
      (node (ref "CONN") (pin "16") (pinfunction "16_MOSI_16") (pintype "bidirectional"))
      (node (ref "IC2") (pin "1") (pinfunction "(MOSI/PCINT13)PB5_1") (pintype "bidirectional"))
    )
    (net (code "32") (name "Net-(A-'1)") (class "Default")
      (node (ref "A") (pin "9") (pinfunction "'1_9") (pintype "bidirectional"))
      (node (ref "LED3") (pin "A") (pinfunction "A_A") (pintype "passive"))
      (node (ref "LED4") (pin "K") (pinfunction "C_K") (pintype "passive"))
      (node (ref "U$1") (pin "9") (pinfunction "OUT2_9") (pintype "bidirectional"))
    )
    (net (code "33") (name "Net-(A-'2)") (class "Default")
      (node (ref "A") (pin "11") (pinfunction "'2_11") (pintype "bidirectional"))
      (node (ref "A_NEXT") (pin "P$1") (pinfunction "1_P$1") (pintype "bidirectional"))
    )
    (net (code "34") (name "Net-(A-'3)") (class "Default")
      (node (ref "A") (pin "13") (pinfunction "'3_13") (pintype "bidirectional"))
      (node (ref "A_PREV") (pin "P$1") (pinfunction "1_P$1") (pintype "bidirectional"))
    )
    (net (code "35") (name "Net-(A-'4)") (class "Default")
      (node (ref "A") (pin "16") (pinfunction "'4_16") (pintype "bidirectional"))
      (node (ref "D1") (pin "C") (pinfunction "C_C") (pintype "passive"))
      (node (ref "T2") (pin "E") (pinfunction "E_E") (pintype "passive"))
    )
    (net (code "36") (name "Net-(A-1)") (class "Default")
      (node (ref "A") (pin "8") (pinfunction "1_8") (pintype "bidirectional"))
      (node (ref "R17") (pin "2") (pinfunction "2_2") (pintype "passive"))
      (node (ref "U$1") (pin "7") (pinfunction "OUT1_7") (pintype "bidirectional"))
    )
    (net (code "37") (name "Net-(A-2)") (class "Default")
      (node (ref "A") (pin "6") (pinfunction "2_6") (pintype "bidirectional"))
      (node (ref "A_NEXT") (pin "P$2") (pinfunction "2_P$2") (pintype "bidirectional"))
    )
    (net (code "38") (name "Net-(A-3)") (class "Default")
      (node (ref "A") (pin "4") (pinfunction "3_4") (pintype "bidirectional"))
      (node (ref "A_PREV") (pin "P$2") (pinfunction "2_P$2") (pintype "bidirectional"))
    )
    (net (code "39") (name "Net-(B-'1)") (class "Default")
      (node (ref "B") (pin "9") (pinfunction "'1_9") (pintype "bidirectional"))
      (node (ref "LED1") (pin "A") (pinfunction "A_A") (pintype "passive"))
      (node (ref "LED2") (pin "K") (pinfunction "C_K") (pintype "passive"))
      (node (ref "U$2") (pin "9") (pinfunction "OUT2_9") (pintype "bidirectional"))
    )
    (net (code "40") (name "Net-(B-'2)") (class "Default")
      (node (ref "B") (pin "11") (pinfunction "'2_11") (pintype "bidirectional"))
      (node (ref "B_NEXT") (pin "P$1") (pinfunction "1_P$1") (pintype "bidirectional"))
    )
    (net (code "41") (name "Net-(B-'3)") (class "Default")
      (node (ref "B") (pin "13") (pinfunction "'3_13") (pintype "bidirectional"))
      (node (ref "B_PREV") (pin "P$1") (pinfunction "1_P$1") (pintype "bidirectional"))
    )
    (net (code "42") (name "Net-(B-'4)") (class "Default")
      (node (ref "B") (pin "16") (pinfunction "'4_16") (pintype "bidirectional"))
      (node (ref "D2") (pin "C") (pinfunction "C_C") (pintype "passive"))
      (node (ref "T1") (pin "E") (pinfunction "E_E") (pintype "passive"))
    )
    (net (code "43") (name "Net-(B-1)") (class "Default")
      (node (ref "B") (pin "8") (pinfunction "1_8") (pintype "bidirectional"))
      (node (ref "R18") (pin "2") (pinfunction "2_2") (pintype "passive"))
      (node (ref "U$2") (pin "7") (pinfunction "OUT1_7") (pintype "bidirectional"))
    )
    (net (code "44") (name "Net-(B-2)") (class "Default")
      (node (ref "B") (pin "6") (pinfunction "2_6") (pintype "bidirectional"))
      (node (ref "B_NEXT") (pin "P$2") (pinfunction "2_P$2") (pintype "bidirectional"))
    )
    (net (code "45") (name "Net-(B-3)") (class "Default")
      (node (ref "B") (pin "4") (pinfunction "3_4") (pintype "bidirectional"))
      (node (ref "B_PREV") (pin "P$2") (pinfunction "2_P$2") (pintype "bidirectional"))
    )
    (net (code "46") (name "Net-(C-'1)") (class "Default")
      (node (ref "C") (pin "9") (pinfunction "'1_9") (pintype "bidirectional"))
      (node (ref "LED5") (pin "A") (pinfunction "A_A") (pintype "passive"))
      (node (ref "LED6") (pin "K") (pinfunction "C_K") (pintype "passive"))
      (node (ref "U$3") (pin "9") (pinfunction "OUT2_9") (pintype "bidirectional"))
    )
    (net (code "47") (name "Net-(C-'2)") (class "Default")
      (node (ref "C") (pin "11") (pinfunction "'2_11") (pintype "bidirectional"))
      (node (ref "C_NEXT") (pin "P$1") (pinfunction "1_P$1") (pintype "bidirectional"))
    )
    (net (code "48") (name "Net-(C-'3)") (class "Default")
      (node (ref "C") (pin "13") (pinfunction "'3_13") (pintype "bidirectional"))
      (node (ref "C_PREV") (pin "P$1") (pinfunction "1_P$1") (pintype "bidirectional"))
    )
    (net (code "49") (name "Net-(C-'4)") (class "Default")
      (node (ref "C") (pin "16") (pinfunction "'4_16") (pintype "bidirectional"))
      (node (ref "D3") (pin "C") (pinfunction "C_C") (pintype "passive"))
      (node (ref "T3") (pin "E") (pinfunction "E_E") (pintype "passive"))
    )
    (net (code "50") (name "Net-(C-1)") (class "Default")
      (node (ref "C") (pin "8") (pinfunction "1_8") (pintype "bidirectional"))
      (node (ref "R20") (pin "2") (pinfunction "2_2") (pintype "passive"))
      (node (ref "U$3") (pin "7") (pinfunction "OUT1_7") (pintype "bidirectional"))
    )
    (net (code "51") (name "Net-(C-2)") (class "Default")
      (node (ref "C") (pin "6") (pinfunction "2_6") (pintype "bidirectional"))
      (node (ref "C_NEXT") (pin "P$2") (pinfunction "2_P$2") (pintype "bidirectional"))
    )
    (net (code "52") (name "Net-(C-3)") (class "Default")
      (node (ref "C") (pin "4") (pinfunction "3_4") (pintype "bidirectional"))
      (node (ref "C_PREV") (pin "P$2") (pinfunction "2_P$2") (pintype "bidirectional"))
    )
    (net (code "53") (name "Net-(CONN-6_5V)") (class "Default")
      (node (ref "CONN") (pin "6") (pinfunction "6_5V_6") (pintype "bidirectional"))
      (node (ref "F3") (pin "1") (pinfunction "1_1") (pintype "passive"))
    )
    (net (code "54") (name "Net-(D-'1)") (class "Default")
      (node (ref "D") (pin "9") (pinfunction "'1_9") (pintype "bidirectional"))
      (node (ref "LED7") (pin "A") (pinfunction "A_A") (pintype "passive"))
      (node (ref "LED8") (pin "K") (pinfunction "C_K") (pintype "passive"))
      (node (ref "U$4") (pin "9") (pinfunction "OUT2_9") (pintype "bidirectional"))
    )
    (net (code "55") (name "Net-(D-'2)") (class "Default")
      (node (ref "D") (pin "11") (pinfunction "'2_11") (pintype "bidirectional"))
      (node (ref "D_NEXT") (pin "P$1") (pinfunction "1_P$1") (pintype "bidirectional"))
    )
    (net (code "56") (name "Net-(D-'3)") (class "Default")
      (node (ref "D") (pin "13") (pinfunction "'3_13") (pintype "bidirectional"))
      (node (ref "D_PREV") (pin "P$1") (pinfunction "1_P$1") (pintype "bidirectional"))
    )
    (net (code "57") (name "Net-(D-'4)") (class "Default")
      (node (ref "D") (pin "16") (pinfunction "'4_16") (pintype "bidirectional"))
      (node (ref "D4") (pin "C") (pinfunction "C_C") (pintype "passive"))
      (node (ref "T4") (pin "E") (pinfunction "E_E") (pintype "passive"))
    )
    (net (code "58") (name "Net-(D-1)") (class "Default")
      (node (ref "D") (pin "8") (pinfunction "1_8") (pintype "bidirectional"))
      (node (ref "R21") (pin "2") (pinfunction "2_2") (pintype "passive"))
      (node (ref "U$4") (pin "7") (pinfunction "OUT1_7") (pintype "bidirectional"))
    )
    (net (code "59") (name "Net-(D-2)") (class "Default")
      (node (ref "D") (pin "6") (pinfunction "2_6") (pintype "bidirectional"))
      (node (ref "D_NEXT") (pin "P$2") (pinfunction "2_P$2") (pintype "bidirectional"))
    )
    (net (code "60") (name "Net-(D-3)") (class "Default")
      (node (ref "D") (pin "4") (pinfunction "3_4") (pintype "bidirectional"))
      (node (ref "D_PREV") (pin "P$2") (pinfunction "2_P$2") (pintype "bidirectional"))
    )
    (net (code "61") (name "Net-(IC1-Pad1)") (class "Default")
      (node (ref "IC1") (pin "1") (pinfunction "1_1") (pintype "bidirectional"))
      (node (ref "R3") (pin "2") (pinfunction "2_2") (pintype "passive"))
    )
    (net (code "62") (name "Net-(IC1A-4)") (class "Default")
      (node (ref "IC1") (pin "7") (pinfunction "4_7") (pintype "bidirectional"))
      (node (ref "R2") (pin "1") (pinfunction "1_1") (pintype "passive"))
      (node (ref "R6") (pin "1") (pinfunction "1_1") (pintype "passive"))
    )
    (net (code "63") (name "Net-(IC1B-1)") (class "Default")
      (node (ref "IC1") (pin "3") (pinfunction "1_3") (pintype "bidirectional"))
      (node (ref "R5") (pin "2") (pinfunction "2_2") (pintype "passive"))
    )
    (net (code "64") (name "Net-(IC1B-4)") (class "Default")
      (node (ref "IC1") (pin "5") (pinfunction "4_5") (pintype "bidirectional"))
      (node (ref "R1") (pin "1") (pinfunction "1_1") (pintype "passive"))
      (node (ref "R4") (pin "1") (pinfunction "1_1") (pintype "passive"))
    )
    (net (code "65") (name "Net-(IC2-AREF)") (class "Default")
      (node (ref "IC2") (pin "27") (pinfunction "AVCC_27") (pintype "power_in"))
      (node (ref "IC2") (pin "29") (pinfunction "AREF_29") (pintype "power_in"))
      (node (ref "L1") (pin "2") (pinfunction "2_2") (pintype "passive"))
    )
    (net (code "66") (name "Net-(IC2-XTAL1)") (class "Default")
      (node (ref "C20") (pin "2") (pinfunction "2_2") (pintype "passive"))
      (node (ref "IC2") (pin "8") (pinfunction "XTAL1_8") (pintype "input"))
      (node (ref "Q1") (pin "2") (pinfunction "2_2") (pintype "passive"))
    )
    (net (code "67") (name "Net-(IC2-XTAL2)") (class "Default")
      (node (ref "C21") (pin "2") (pinfunction "2_2") (pintype "passive"))
      (node (ref "IC2") (pin "7") (pinfunction "XTAL2_7") (pintype "output"))
      (node (ref "Q1") (pin "1") (pinfunction "1_1") (pintype "passive"))
    )
    (net (code "68") (name "Net-(IC3A-+IN)") (class "Default")
      (node (ref "C9") (pin "1") (pinfunction "1_1") (pintype "passive"))
      (node (ref "IC3") (pin "3") (pinfunction "+IN_3") (pintype "input"))
      (node (ref "R9") (pin "2") (pinfunction "2_2") (pintype "passive"))
    )
    (net (code "69") (name "Net-(IC3A--IN)") (class "Default")
      (node (ref "IC3") (pin "2") (pinfunction "-IN_2") (pintype "input"))
      (node (ref "R14") (pin "1") (pinfunction "1_1") (pintype "passive"))
      (node (ref "R16") (pin "1") (pinfunction "1_1") (pintype "passive"))
    )
    (net (code "70") (name "Net-(IC3B-+IN)") (class "Default")
      (node (ref "C10") (pin "1") (pinfunction "1_1") (pintype "passive"))
      (node (ref "IC3") (pin "5") (pinfunction "+IN_5") (pintype "input"))
      (node (ref "R10") (pin "2") (pinfunction "2_2") (pintype "passive"))
    )
    (net (code "71") (name "Net-(IC3B--IN)") (class "Default")
      (node (ref "IC3") (pin "6") (pinfunction "-IN_6") (pintype "input"))
      (node (ref "R13") (pin "1") (pinfunction "1_1") (pintype "passive"))
      (node (ref "R15") (pin "1") (pinfunction "1_1") (pintype "passive"))
    )
    (net (code "72") (name "Net-(IC3C-+IN)") (class "Default")
      (node (ref "C17") (pin "1") (pinfunction "1_1") (pintype "passive"))
      (node (ref "IC3") (pin "10") (pinfunction "+IN_10") (pintype "input"))
      (node (ref "R29") (pin "2") (pinfunction "2_2") (pintype "passive"))
    )
    (net (code "73") (name "Net-(IC3C--IN)") (class "Default")
      (node (ref "IC3") (pin "9") (pinfunction "-IN_9") (pintype "input"))
      (node (ref "R22") (pin "1") (pinfunction "1_1") (pintype "passive"))
      (node (ref "R23") (pin "1") (pinfunction "1_1") (pintype "passive"))
    )
    (net (code "74") (name "Net-(IC3D-+IN)") (class "Default")
      (node (ref "C16") (pin "1") (pinfunction "1_1") (pintype "passive"))
      (node (ref "IC3") (pin "12") (pinfunction "+IN_12") (pintype "input"))
      (node (ref "R28") (pin "2") (pinfunction "2_2") (pintype "passive"))
    )
    (net (code "75") (name "Net-(IC3D--IN)") (class "Default")
      (node (ref "IC3") (pin "13") (pinfunction "-IN_13") (pintype "input"))
      (node (ref "R24") (pin "1") (pinfunction "1_1") (pintype "passive"))
      (node (ref "R25") (pin "1") (pinfunction "1_1") (pintype "passive"))
    )
    (net (code "76") (name "Net-(IC4-Pad1)") (class "Default")
      (node (ref "IC4") (pin "1") (pinfunction "1_1") (pintype "bidirectional"))
      (node (ref "R33") (pin "2") (pinfunction "2_2") (pintype "passive"))
    )
    (net (code "77") (name "Net-(IC4A-4)") (class "Default")
      (node (ref "IC4") (pin "7") (pinfunction "4_7") (pintype "bidirectional"))
      (node (ref "R34") (pin "1") (pinfunction "1_1") (pintype "passive"))
      (node (ref "R37") (pin "1") (pinfunction "1_1") (pintype "passive"))
    )
    (net (code "78") (name "Net-(IC4B-1)") (class "Default")
      (node (ref "IC4") (pin "3") (pinfunction "1_3") (pintype "bidirectional"))
      (node (ref "R32") (pin "2") (pinfunction "2_2") (pintype "passive"))
    )
    (net (code "79") (name "Net-(IC4B-4)") (class "Default")
      (node (ref "IC4") (pin "5") (pinfunction "4_5") (pintype "bidirectional"))
      (node (ref "R35") (pin "1") (pinfunction "1_1") (pintype "passive"))
      (node (ref "R36") (pin "1") (pinfunction "1_1") (pintype "passive"))
    )
    (net (code "80") (name "Net-(LED1-C)") (class "Default")
      (node (ref "LED1") (pin "K") (pinfunction "C_K") (pintype "passive"))
      (node (ref "LED2") (pin "A") (pinfunction "A_A") (pintype "passive"))
      (node (ref "R18") (pin "1") (pinfunction "1_1") (pintype "passive"))
    )
    (net (code "81") (name "Net-(LED3-C)") (class "Default")
      (node (ref "LED3") (pin "K") (pinfunction "C_K") (pintype "passive"))
      (node (ref "LED4") (pin "A") (pinfunction "A_A") (pintype "passive"))
      (node (ref "R17") (pin "1") (pinfunction "1_1") (pintype "passive"))
    )
    (net (code "82") (name "Net-(LED5-C)") (class "Default")
      (node (ref "LED5") (pin "K") (pinfunction "C_K") (pintype "passive"))
      (node (ref "LED6") (pin "A") (pinfunction "A_A") (pintype "passive"))
      (node (ref "R20") (pin "1") (pinfunction "1_1") (pintype "passive"))
    )
    (net (code "83") (name "Net-(LED7-C)") (class "Default")
      (node (ref "LED7") (pin "K") (pinfunction "C_K") (pintype "passive"))
      (node (ref "LED8") (pin "A") (pinfunction "A_A") (pintype "passive"))
      (node (ref "R21") (pin "1") (pinfunction "1_1") (pintype "passive"))
    )
    (net (code "84") (name "Net-(R2-Pad2)") (class "Default")
      (node (ref "R2") (pin "2") (pinfunction "2_2") (pintype "passive"))
      (node (ref "T2") (pin "B") (pinfunction "B_B") (pintype "passive"))
    )
    (net (code "85") (name "Net-(R4-Pad2)") (class "Default")
      (node (ref "R4") (pin "2") (pinfunction "2_2") (pintype "passive"))
      (node (ref "T1") (pin "B") (pinfunction "B_B") (pintype "passive"))
    )
    (net (code "86") (name "Net-(R36-Pad2)") (class "Default")
      (node (ref "R36") (pin "2") (pinfunction "2_2") (pintype "passive"))
      (node (ref "T3") (pin "B") (pinfunction "B_B") (pintype "passive"))
    )
    (net (code "87") (name "Net-(R37-Pad2)") (class "Default")
      (node (ref "R37") (pin "2") (pinfunction "2_2") (pintype "passive"))
      (node (ref "T4") (pin "B") (pinfunction "B_B") (pintype "passive"))
    )
    (net (code "88") (name "Net-(U$1-ALERT)") (class "Default")
      (node (ref "R7") (pin "1") (pinfunction "1_1") (pintype "passive"))
      (node (ref "U$1") (pin "11") (pinfunction "ALERT_11") (pintype "bidirectional"))
    )
    (net (code "89") (name "Net-(U$1-P_GND)") (class "Default")
      (node (ref "R11") (pin "1") (pinfunction "1_1") (pintype "passive"))
      (node (ref "R9") (pin "1") (pinfunction "1_1") (pintype "passive"))
      (node (ref "U$1") (pin "10") (pinfunction "P_GND_10") (pintype "bidirectional"))
    )
    (net (code "90") (name "Net-(U$1-VCC)") (class "Default")
      (node (ref "C1") (pin "+") (pinfunction "+_+") (pintype "passive"))
      (node (ref "C7") (pin "2") (pinfunction "2_2") (pintype "passive"))
      (node (ref "F2") (pin "1") (pinfunction "1_1") (pintype "passive"))
      (node (ref "U$1") (pin "5") (pinfunction "VCC_5") (pintype "bidirectional"))
    )
    (net (code "91") (name "Net-(U$1-VREG)") (class "Default")
      (node (ref "C3") (pin "1") (pinfunction "1_1") (pintype "passive"))
      (node (ref "U$1") (pin "15") (pinfunction "VREG_15") (pintype "bidirectional"))
    )
    (net (code "92") (name "Net-(U$2-ALERT)") (class "Default")
      (node (ref "R8") (pin "1") (pinfunction "1_1") (pintype "passive"))
      (node (ref "U$2") (pin "11") (pinfunction "ALERT_11") (pintype "bidirectional"))
    )
    (net (code "93") (name "Net-(U$2-P_GND)") (class "Default")
      (node (ref "R10") (pin "1") (pinfunction "1_1") (pintype "passive"))
      (node (ref "R12") (pin "1") (pinfunction "1_1") (pintype "passive"))
      (node (ref "U$2") (pin "10") (pinfunction "P_GND_10") (pintype "bidirectional"))
    )
    (net (code "94") (name "Net-(U$2-VCC)") (class "Default")
      (node (ref "C2") (pin "+") (pinfunction "+_+") (pintype "passive"))
      (node (ref "C8") (pin "2") (pinfunction "2_2") (pintype "passive"))
      (node (ref "F1") (pin "1") (pinfunction "1_1") (pintype "passive"))
      (node (ref "U$2") (pin "5") (pinfunction "VCC_5") (pintype "bidirectional"))
    )
    (net (code "95") (name "Net-(U$2-VREG)") (class "Default")
      (node (ref "C4") (pin "1") (pinfunction "1_1") (pintype "passive"))
      (node (ref "U$2") (pin "15") (pinfunction "VREG_15") (pintype "bidirectional"))
    )
    (net (code "96") (name "Net-(U$3-ALERT)") (class "Default")
      (node (ref "R30") (pin "1") (pinfunction "1_1") (pintype "passive"))
      (node (ref "U$3") (pin "11") (pinfunction "ALERT_11") (pintype "bidirectional"))
    )
    (net (code "97") (name "Net-(U$3-P_GND)") (class "Default")
      (node (ref "R26") (pin "1") (pinfunction "1_1") (pintype "passive"))
      (node (ref "R28") (pin "1") (pinfunction "1_1") (pintype "passive"))
      (node (ref "U$3") (pin "10") (pinfunction "P_GND_10") (pintype "bidirectional"))
    )
    (net (code "98") (name "Net-(U$3-VCC)") (class "Default")
      (node (ref "C18") (pin "2") (pinfunction "2_2") (pintype "passive"))
      (node (ref "C27") (pin "+") (pinfunction "+_+") (pintype "passive"))
      (node (ref "F4") (pin "1") (pinfunction "1_1") (pintype "passive"))
      (node (ref "U$3") (pin "5") (pinfunction "VCC_5") (pintype "bidirectional"))
    )
    (net (code "99") (name "Net-(U$3-VREG)") (class "Default")
      (node (ref "C24") (pin "1") (pinfunction "1_1") (pintype "passive"))
      (node (ref "U$3") (pin "15") (pinfunction "VREG_15") (pintype "bidirectional"))
    )
    (net (code "100") (name "Net-(U$4-ALERT)") (class "Default")
      (node (ref "R31") (pin "1") (pinfunction "1_1") (pintype "passive"))
      (node (ref "U$4") (pin "11") (pinfunction "ALERT_11") (pintype "bidirectional"))
    )
    (net (code "101") (name "Net-(U$4-P_GND)") (class "Default")
      (node (ref "R27") (pin "1") (pinfunction "1_1") (pintype "passive"))
      (node (ref "R29") (pin "1") (pinfunction "1_1") (pintype "passive"))
      (node (ref "U$4") (pin "10") (pinfunction "P_GND_10") (pintype "bidirectional"))
    )
    (net (code "102") (name "Net-(U$4-VCC)") (class "Default")
      (node (ref "C19") (pin "2") (pinfunction "2_2") (pintype "passive"))
      (node (ref "C26") (pin "+") (pinfunction "+_+") (pintype "passive"))
      (node (ref "F5") (pin "1") (pinfunction "1_1") (pintype "passive"))
      (node (ref "U$4") (pin "5") (pinfunction "VCC_5") (pintype "bidirectional"))
    )
    (net (code "103") (name "Net-(U$4-VREG)") (class "Default")
      (node (ref "C25") (pin "1") (pinfunction "1_1") (pintype "passive"))
      (node (ref "U$4") (pin "15") (pinfunction "VREG_15") (pintype "bidirectional"))
    )
    (net (code "104") (name "SCK") (class "Default")
      (node (ref "CONN") (pin "13") (pinfunction "13_SCK_13") (pintype "bidirectional"))
      (node (ref "IC2") (pin "3") (pinfunction "(SCK/PCINT15)PB7_3") (pintype "bidirectional"))
    )
    (net (code "105") (name "TCK") (class "Default")
      (node (ref "IC2") (pin "21") (pinfunction "(TCK/PCINT18)PC2_21") (pintype "bidirectional"))
      (node (ref "JP1") (pin "1") (pinfunction "1_1") (pintype "passive"))
    )
    (net (code "106") (name "TDI") (class "Default")
      (node (ref "IC2") (pin "24") (pinfunction "(TDI/PCINT21)PC5_24") (pintype "bidirectional"))
      (node (ref "JP1") (pin "9") (pinfunction "9_9") (pintype "passive"))
    )
    (net (code "107") (name "TDO") (class "Default")
      (node (ref "IC2") (pin "23") (pinfunction "(TDO/PCINT20)PC4_23") (pintype "bidirectional"))
      (node (ref "JP1") (pin "3") (pinfunction "3_3") (pintype "passive"))
    )
    (net (code "108") (name "TMS") (class "Default")
      (node (ref "IC2") (pin "22") (pinfunction "(TMS/PCINT19)PC3_22") (pintype "bidirectional"))
      (node (ref "JP1") (pin "5") (pinfunction "5_5") (pintype "passive"))
    )
    (net (code "109") (name "unconnected-(CONN-10_3.3V-Pad10)") (class "Default")
      (node (ref "CONN") (pin "10") (pinfunction "10_3.3V_10") (pintype "bidirectional"))
    )
    (net (code "110") (name "unconnected-(JP1-Pad4)") (class "Default")
      (node (ref "JP1") (pin "4") (pinfunction "4_4") (pintype "passive"))
    )
    (net (code "111") (name "unconnected-(JP1-Pad8)") (class "Default")
      (node (ref "JP1") (pin "8") (pinfunction "8_8") (pintype "passive"))
    )
    (net (code "112") (name "unconnected-(U$1-NC-Pad6)") (class "Default")
      (node (ref "U$1") (pin "6") (pinfunction "NC_6") (pintype "bidirectional"))
    )
    (net (code "113") (name "unconnected-(U$2-NC-Pad6)") (class "Default")
      (node (ref "U$2") (pin "6") (pinfunction "NC_6") (pintype "bidirectional"))
    )
    (net (code "114") (name "unconnected-(U$3-NC-Pad6)") (class "Default")
      (node (ref "U$3") (pin "6") (pinfunction "NC_6") (pintype "bidirectional"))
    )
    (net (code "115") (name "unconnected-(U$4-NC-Pad6)") (class "Default")
      (node (ref "U$4") (pin "6") (pinfunction "NC_6") (pintype "bidirectional"))
    )
  )
)
